# Sheet.net
KiCad netlist of a schematic drawn in Altium Designer
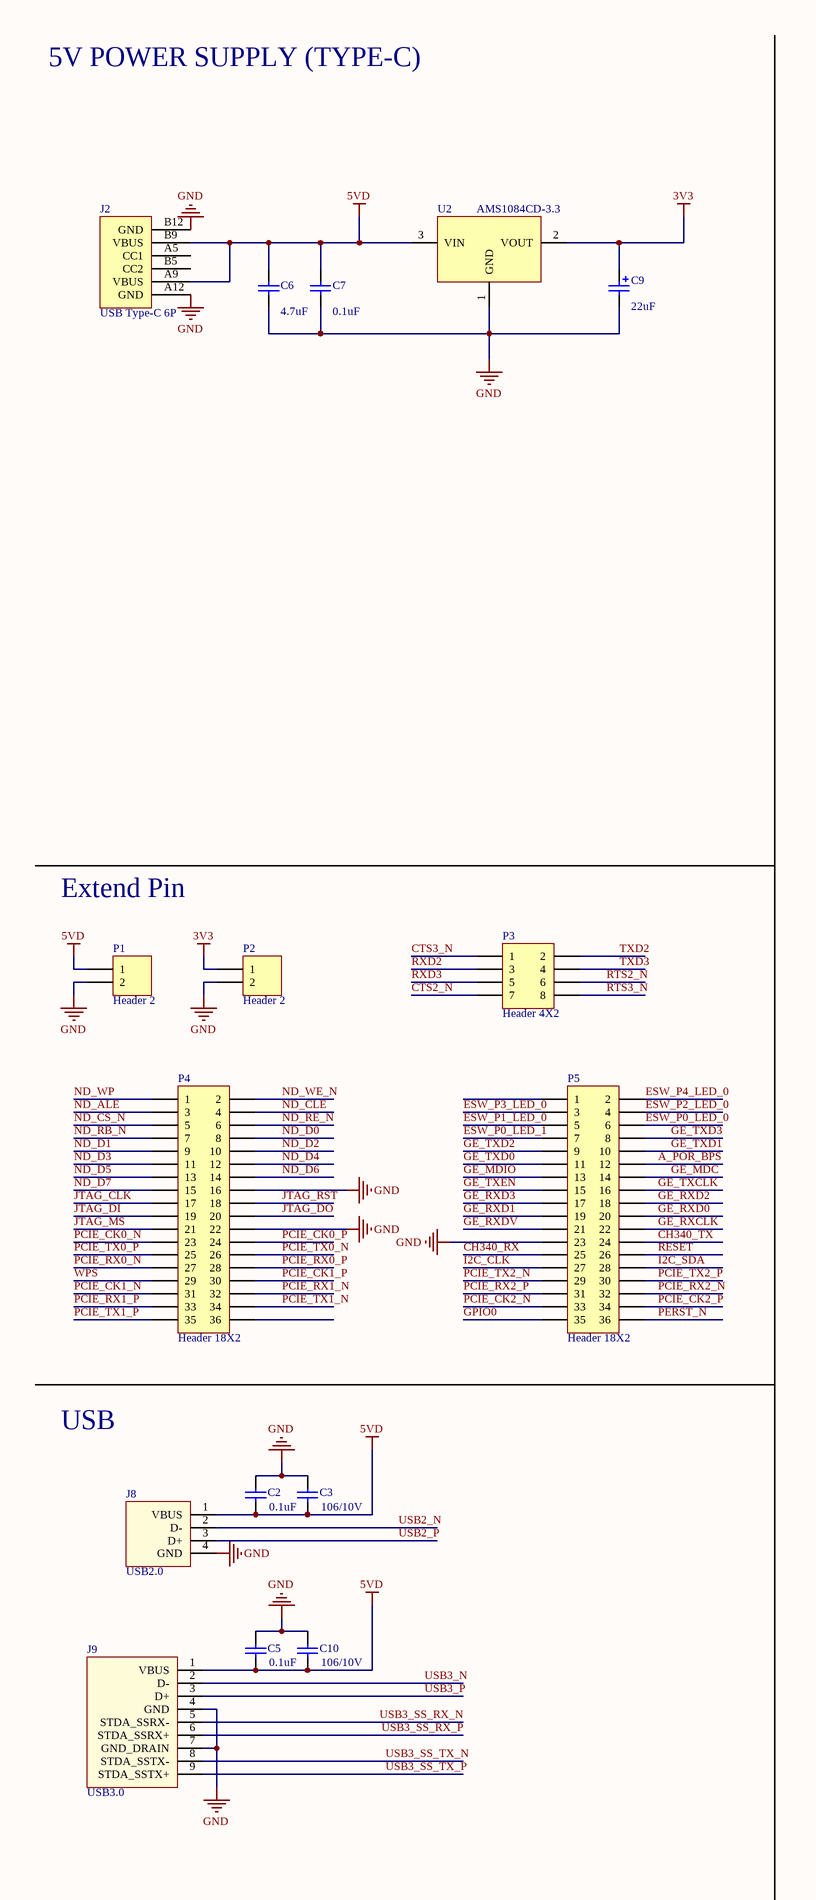
[diagram p0: Sheet.SchDoc, left]
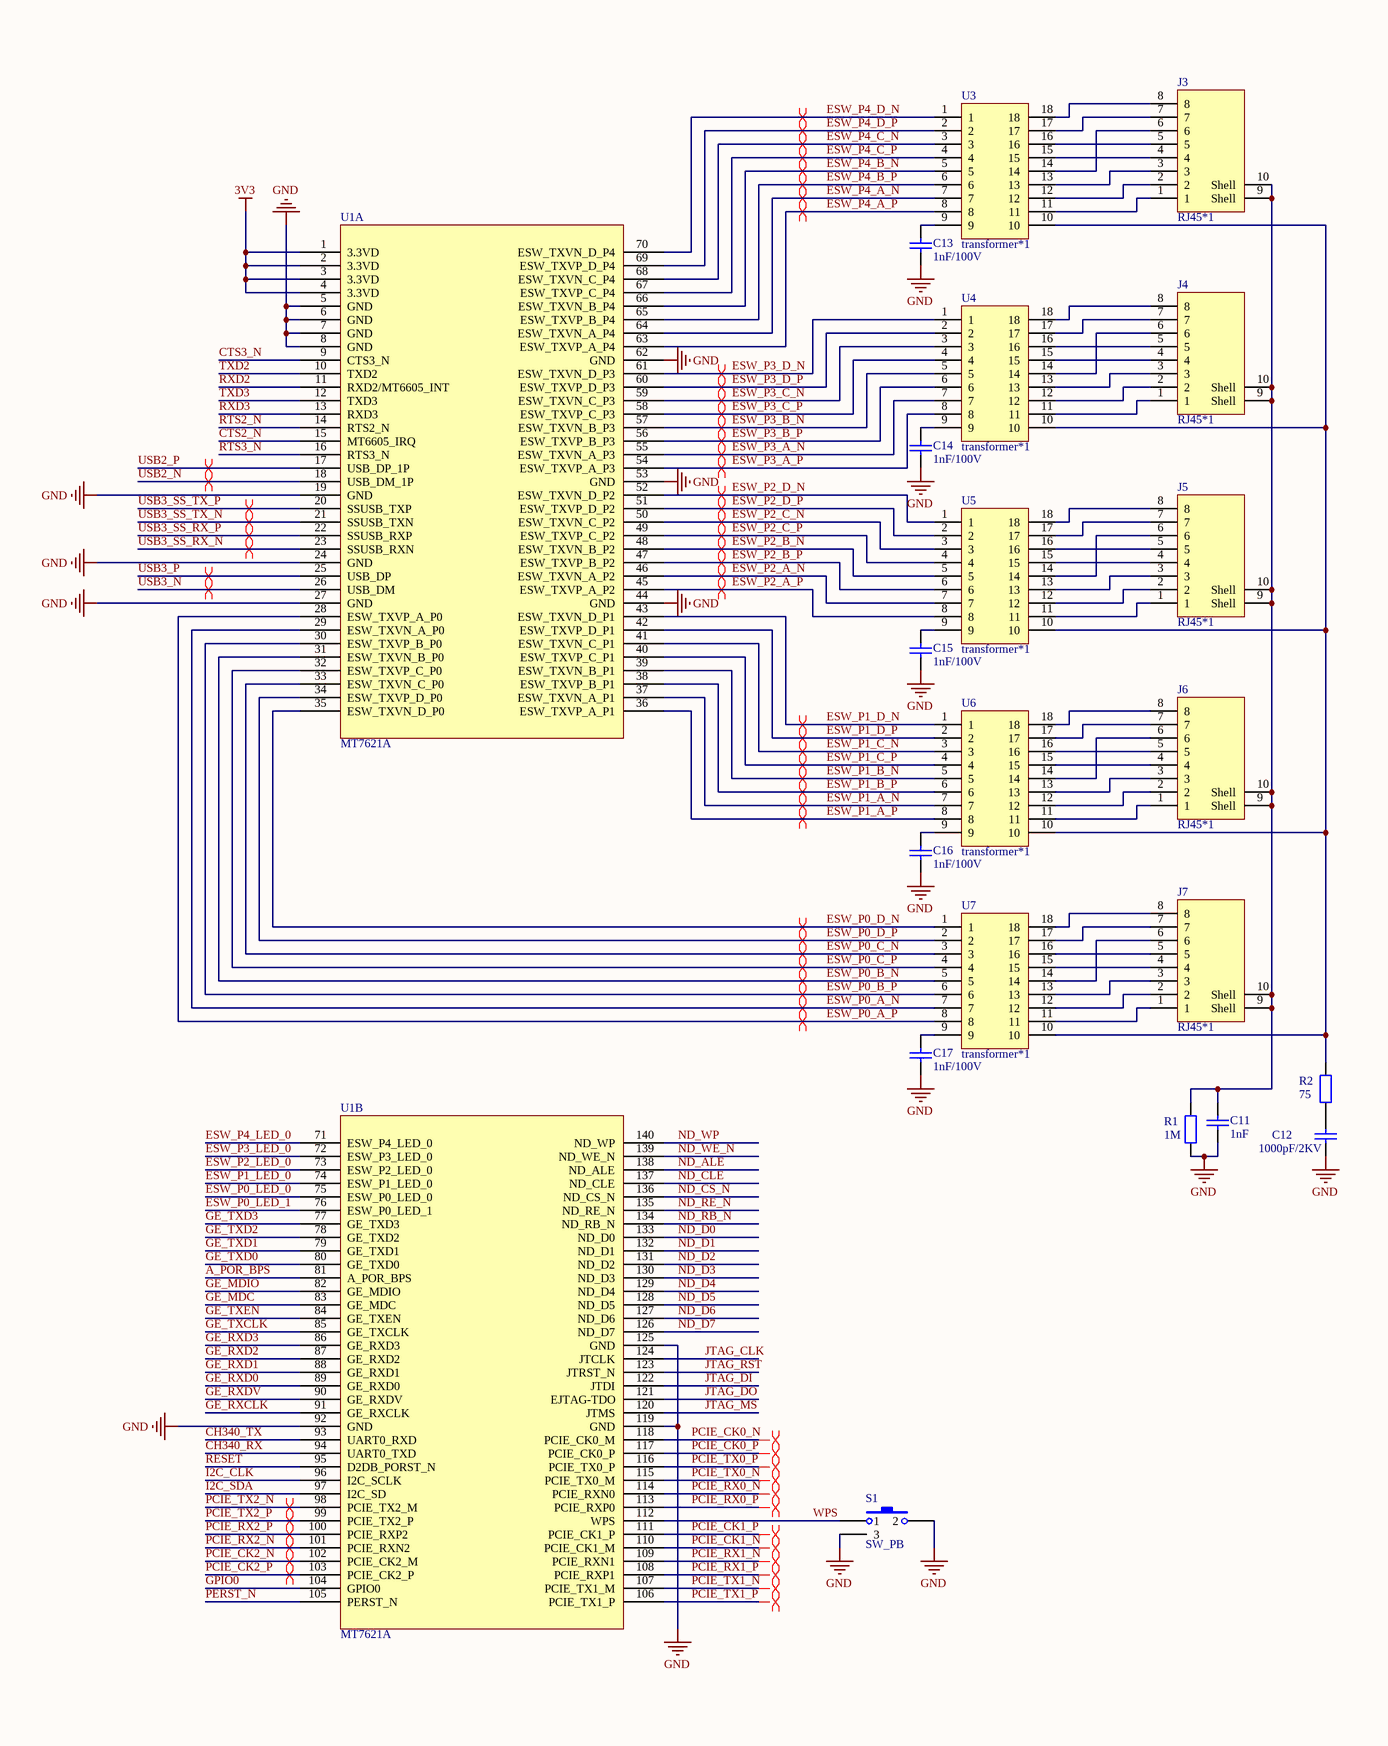
[diagram p1: Sheet.SchDoc, right]

(export (version "E")
  (design (tool "Eeschema 10.0.6"))
  (components
    (comp (ref "C2")
      (value "0.1uF")
      (footprint "6-0805")
      (description "Capacitor")
      (fields (field (name "Comment") "Cap") (field (name "PUBLISHER") "Altium Limited"))
      (libsource (lib "Miscellaneous Devices") (part "Cap"))
    )
    (comp (ref "C3")
      (value "106/10V")
      (footprint "6-0805")
      (description "Capacitor")
      (fields (field (name "Comment") "Cap") (field (name "PUBLISHER") "Altium Limited"))
      (libsource (lib "Miscellaneous Devices") (part "Cap"))
    )
    (comp (ref "C5")
      (value "0.1uF")
      (footprint "6-0805")
      (description "Capacitor")
      (fields (field (name "Comment") "Cap") (field (name "PUBLISHER") "Altium Limited"))
      (libsource (lib "Miscellaneous Devices") (part "Cap"))
    )
    (comp (ref "C6")
      (value "4.7uF")
      (footprint "6-0805")
      (description "Capacitor")
      (fields (field (name "Comment") "Cap") (field (name "PUBLISHER") "Altium Limited"))
      (libsource (lib "Miscellaneous Devices") (part "Cap"))
    )
    (comp (ref "C7")
      (value "0.1uF")
      (footprint "6-0805")
      (description "Capacitor")
      (fields (field (name "Comment") "Cap") (field (name "PUBLISHER") "Altium Limited"))
      (libsource (lib "Miscellaneous Devices") (part "Cap"))
    )
    (comp (ref "C9")
      (value "22uF")
      (footprint "3528B")
      (description "Polarized Capacitor (Axial)")
      (fields (field (name "Comment") "Cap Pol2") (field (name "PUBLISHER") "Altium Limited"))
      (libsource (lib "Miscellaneous Devices") (part "Cap Pol2"))
    )
    (comp (ref "C10")
      (value "106/10V")
      (footprint "6-0805")
      (description "Capacitor")
      (fields (field (name "Comment") "Cap") (field (name "PUBLISHER") "Altium Limited"))
      (libsource (lib "Miscellaneous Devices") (part "Cap"))
    )
    (comp (ref "C11")
      (value "1nF")
      (footprint "8-1206")
      (description "Capacitor")
      (fields (field (name "Comment") "Cap") (field (name "PUBLISHER") "Altium Limited"))
      (libsource (lib "Miscellaneous Devices") (part "Cap"))
    )
    (comp (ref "C12")
      (value "1000pF/2KV")
      (footprint "8-1206")
      (description "Capacitor")
      (fields (field (name "Comment") "Cap") (field (name "PUBLISHER") "Altium Limited"))
      (libsource (lib "Miscellaneous Devices") (part "Cap"))
    )
    (comp (ref "C13")
      (value "1nF/100V")
      (footprint "6-0805")
      (description "Capacitor")
      (fields (field (name "Comment") "Cap") (field (name "PUBLISHER") "Altium Limited"))
      (libsource (lib "Miscellaneous Devices") (part "Cap"))
    )
    (comp (ref "C14")
      (value "1nF/100V")
      (footprint "6-0805")
      (description "Capacitor")
      (fields (field (name "Comment") "Cap") (field (name "PUBLISHER") "Altium Limited"))
      (libsource (lib "Miscellaneous Devices") (part "Cap"))
    )
    (comp (ref "C15")
      (value "1nF/100V")
      (footprint "6-0805")
      (description "Capacitor")
      (fields (field (name "Comment") "Cap") (field (name "PUBLISHER") "Altium Limited"))
      (libsource (lib "Miscellaneous Devices") (part "Cap"))
    )
    (comp (ref "C16")
      (value "1nF/100V")
      (footprint "6-0805")
      (description "Capacitor")
      (fields (field (name "Comment") "Cap") (field (name "PUBLISHER") "Altium Limited"))
      (libsource (lib "Miscellaneous Devices") (part "Cap"))
    )
    (comp (ref "C17")
      (value "1nF/100V")
      (footprint "6-0805")
      (description "Capacitor")
      (fields (field (name "Comment") "Cap") (field (name "PUBLISHER") "Altium Limited"))
      (libsource (lib "Miscellaneous Devices") (part "Cap"))
    )
    (comp (ref "J2")
      (value "USB Type-C 6P")
      (footprint "USB Type-C 6P")
      (libsource (lib "7621_cmp") (part "USB Type-C 6P"))
    )
    (comp (ref "J3") (value "RJ45*1") (libsource (lib "7621_cmp") (part "RJ45*1")))
    (comp (ref "J4") (value "RJ45*1") (libsource (lib "7621_cmp") (part "RJ45*1")))
    (comp (ref "J5") (value "RJ45*1") (libsource (lib "7621_cmp") (part "RJ45*1")))
    (comp (ref "J6") (value "RJ45*1") (libsource (lib "7621_cmp") (part "RJ45*1")))
    (comp (ref "J7") (value "RJ45*1") (libsource (lib "7621_cmp") (part "RJ45*1")))
    (comp (ref "J8") (value "USB2.0") (footprint "USB2.0") (libsource (lib "7621_cmp") (part "USB2.0")))
    (comp (ref "J9") (value "USB3.0") (footprint "USB3.0_0") (libsource (lib "7621_cmp") (part "USB3.0")))
    (comp (ref "P1")
      (value "Header 2")
      (footprint "HDR1X2")
      (description "Header, 2-Pin")
      (fields (field (name "PUBLISHER") "Altium Limited"))
      (libsource (lib "Miscellaneous Connectors") (part "Header 2"))
    )
    (comp (ref "P2")
      (value "Header 2")
      (footprint "HDR1X2")
      (description "Header, 2-Pin")
      (fields (field (name "PUBLISHER") "Altium Limited"))
      (libsource (lib "Miscellaneous Connectors") (part "Header 2"))
    )
    (comp (ref "P3")
      (value "Header 4X2")
      (footprint "HDR2X4")
      (description "Header, 4-Pin, Dual row")
      (fields (field (name "PUBLISHER") "Altium Limited"))
      (libsource (lib "Miscellaneous Connectors") (part "Header 4X2"))
    )
    (comp (ref "P4")
      (value "Header 18X2")
      (footprint "HDR2X18")
      (description "Header, 18-Pin, Dual row")
      (fields (field (name "PUBLISHER") "Altium Limited"))
      (libsource (lib "Miscellaneous Connectors") (part "Header 18X2"))
    )
    (comp (ref "P5")
      (value "Header 18X2")
      (footprint "HDR2X18")
      (description "Header, 18-Pin, Dual row")
      (fields (field (name "PUBLISHER") "Altium Limited"))
      (libsource (lib "Miscellaneous Connectors") (part "Header 18X2"))
    )
    (comp (ref "R1")
      (value "1M")
      (footprint "8-1206")
      (description "Resistor")
      (fields (field (name "Comment") "Res2") (field (name "PUBLISHER") "Altium Limited"))
      (libsource (lib "Miscellaneous Devices") (part "Res2"))
    )
    (comp (ref "R2")
      (value "75")
      (footprint "8-1206")
      (description "Resistor")
      (fields (field (name "Comment") "Res2") (field (name "PUBLISHER") "Altium Limited"))
      (libsource (lib "Miscellaneous Devices") (part "Res2"))
    )
    (comp (ref "S1") (value "SW_PB") (footprint "SW_PB") (libsource (lib "7621_cmp") (part "SW_PB")))
    (comp (ref "U1") (value "MT7621A") (footprint "HLK-7621") (libsource (lib "7621_cmp") (part "MT7621A")))
    (comp (ref "U2")
      (value "AMS1084CD-3.3")
      (footprint "TO252")
      (libsource (lib "7621_cmp") (part "AMS1084CD-3.3"))
    )
    (comp (ref "U3")
      (value "transformer*1")
      (footprint "transformer_G1801D")
      (libsource (lib "7621_cmp") (part "transformer*1"))
    )
    (comp (ref "U4")
      (value "transformer*1")
      (footprint "transformer_G1801D")
      (libsource (lib "7621_cmp") (part "transformer*1"))
    )
    (comp (ref "U5")
      (value "transformer*1")
      (footprint "transformer_G1801D")
      (libsource (lib "7621_cmp") (part "transformer*1"))
    )
    (comp (ref "U6")
      (value "transformer*1")
      (footprint "transformer_G1801D")
      (libsource (lib "7621_cmp") (part "transformer*1"))
    )
    (comp (ref "U7")
      (value "transformer*1")
      (footprint "transformer_G1801D")
      (libsource (lib "7621_cmp") (part "transformer*1"))
    )
  )
  (nets
    (net (code "1") (name "/A_POR_BPS") (class "Default")
      (node (ref "P5") (pin "12") (pinfunction "12_12") (pintype "passive"))
      (node (ref "U1") (pin "81") (pinfunction "A_POR_BPS_81") (pintype "passive"))
    )
    (net (code "2") (name "/CH340_RX") (class "Default")
      (node (ref "P5") (pin "25") (pinfunction "25_25") (pintype "passive"))
      (node (ref "U1") (pin "94") (pinfunction "UART0_TXD_94") (pintype "passive"))
    )
    (net (code "3") (name "/CH340_TX") (class "Default")
      (node (ref "P5") (pin "24") (pinfunction "24_24") (pintype "passive"))
      (node (ref "U1") (pin "93") (pinfunction "UART0_RXD_93") (pintype "passive"))
    )
    (net (code "4") (name "/CTS2_N") (class "Default")
      (node (ref "P3") (pin "7") (pinfunction "7_7") (pintype "passive"))
      (node (ref "U1") (pin "15") (pinfunction "MT6605_IRQ_15") (pintype "passive"))
    )
    (net (code "5") (name "/CTS3_N") (class "Default")
      (node (ref "P3") (pin "1") (pinfunction "1_1") (pintype "passive"))
      (node (ref "U1") (pin "9") (pinfunction "CTS3_N_9") (pintype "passive"))
    )
    (net (code "6") (name "/ESW_P0_A_N") (class "Default")
      (node (ref "U1") (pin "29") (pinfunction "ESW_TXVN_A_P0_29") (pintype "passive"))
      (node (ref "U7") (pin "7") (pinfunction "7_7") (pintype "passive"))
    )
    (net (code "7") (name "/ESW_P0_A_P") (class "Default")
      (node (ref "U1") (pin "28") (pinfunction "ESW_TXVP_A_P0_28") (pintype "passive"))
      (node (ref "U7") (pin "8") (pinfunction "8_8") (pintype "passive"))
    )
    (net (code "8") (name "/ESW_P0_B_N") (class "Default")
      (node (ref "U1") (pin "31") (pinfunction "ESW_TXVN_B_P0_31") (pintype "passive"))
      (node (ref "U7") (pin "5") (pinfunction "5_5") (pintype "passive"))
    )
    (net (code "9") (name "/ESW_P0_B_P") (class "Default")
      (node (ref "U1") (pin "30") (pinfunction "ESW_TXVP_B_P0_30") (pintype "passive"))
      (node (ref "U7") (pin "6") (pinfunction "6_6") (pintype "passive"))
    )
    (net (code "10") (name "/ESW_P0_C_N") (class "Default")
      (node (ref "U1") (pin "33") (pinfunction "ESW_TXVN_C_P0_33") (pintype "passive"))
      (node (ref "U7") (pin "3") (pinfunction "3_3") (pintype "passive"))
    )
    (net (code "11") (name "/ESW_P0_C_P") (class "Default")
      (node (ref "U1") (pin "32") (pinfunction "ESW_TXVP_C_P0_32") (pintype "passive"))
      (node (ref "U7") (pin "4") (pinfunction "4_4") (pintype "passive"))
    )
    (net (code "12") (name "/ESW_P0_D_N") (class "Default")
      (node (ref "U1") (pin "35") (pinfunction "ESW_TXVN_D_P0_35") (pintype "passive"))
      (node (ref "U7") (pin "1") (pinfunction "1_1") (pintype "passive"))
    )
    (net (code "13") (name "/ESW_P0_D_P") (class "Default")
      (node (ref "U1") (pin "34") (pinfunction "ESW_TXVP_D_P0_34") (pintype "passive"))
      (node (ref "U7") (pin "2") (pinfunction "2_2") (pintype "passive"))
    )
    (net (code "14") (name "/ESW_P0_LED_0") (class "Default")
      (node (ref "P5") (pin "6") (pinfunction "6_6") (pintype "passive"))
      (node (ref "U1") (pin "75") (pinfunction "ESW_P0_LED_0_75") (pintype "passive"))
    )
    (net (code "15") (name "/ESW_P0_LED_1") (class "Default")
      (node (ref "P5") (pin "7") (pinfunction "7_7") (pintype "passive"))
      (node (ref "U1") (pin "76") (pinfunction "ESW_P0_LED_1_76") (pintype "passive"))
    )
    (net (code "16") (name "/ESW_P1_A_N") (class "Default")
      (node (ref "U1") (pin "37") (pinfunction "ESW_TXVN_A_P1_37") (pintype "passive"))
      (node (ref "U6") (pin "7") (pinfunction "7_7") (pintype "passive"))
    )
    (net (code "17") (name "/ESW_P1_A_P") (class "Default")
      (node (ref "U1") (pin "36") (pinfunction "ESW_TXVP_A_P1_36") (pintype "passive"))
      (node (ref "U6") (pin "8") (pinfunction "8_8") (pintype "passive"))
    )
    (net (code "18") (name "/ESW_P1_B_N") (class "Default")
      (node (ref "U1") (pin "39") (pinfunction "ESW_TXVN_B_P1_39") (pintype "passive"))
      (node (ref "U6") (pin "5") (pinfunction "5_5") (pintype "passive"))
    )
    (net (code "19") (name "/ESW_P1_B_P") (class "Default")
      (node (ref "U1") (pin "38") (pinfunction "ESW_TXVP_B_P1_38") (pintype "passive"))
      (node (ref "U6") (pin "6") (pinfunction "6_6") (pintype "passive"))
    )
    (net (code "20") (name "/ESW_P1_C_N") (class "Default")
      (node (ref "U1") (pin "41") (pinfunction "ESW_TXVN_C_P1_41") (pintype "passive"))
      (node (ref "U6") (pin "3") (pinfunction "3_3") (pintype "passive"))
    )
    (net (code "21") (name "/ESW_P1_C_P") (class "Default")
      (node (ref "U1") (pin "40") (pinfunction "ESW_TXVP_C_P1_40") (pintype "passive"))
      (node (ref "U6") (pin "4") (pinfunction "4_4") (pintype "passive"))
    )
    (net (code "22") (name "/ESW_P1_D_N") (class "Default")
      (node (ref "U1") (pin "43") (pinfunction "ESW_TXVN_D_P1_43") (pintype "passive"))
      (node (ref "U6") (pin "1") (pinfunction "1_1") (pintype "passive"))
    )
    (net (code "23") (name "/ESW_P1_D_P") (class "Default")
      (node (ref "U1") (pin "42") (pinfunction "ESW_TXVP_D_P1_42") (pintype "passive"))
      (node (ref "U6") (pin "2") (pinfunction "2_2") (pintype "passive"))
    )
    (net (code "24") (name "/ESW_P1_LED_0") (class "Default")
      (node (ref "P5") (pin "5") (pinfunction "5_5") (pintype "passive"))
      (node (ref "U1") (pin "74") (pinfunction "ESW_P1_LED_0_74") (pintype "passive"))
    )
    (net (code "25") (name "/ESW_P2_A_N") (class "Default")
      (node (ref "U1") (pin "46") (pinfunction "ESW_TXVN_A_P2_46") (pintype "passive"))
      (node (ref "U5") (pin "7") (pinfunction "7_7") (pintype "passive"))
    )
    (net (code "26") (name "/ESW_P2_A_P") (class "Default")
      (node (ref "U1") (pin "45") (pinfunction "ESW_TXVP_A_P2_45") (pintype "passive"))
      (node (ref "U5") (pin "8") (pinfunction "8_8") (pintype "passive"))
    )
    (net (code "27") (name "/ESW_P2_B_N") (class "Default")
      (node (ref "U1") (pin "48") (pinfunction "ESW_TXVN_B_P2_48") (pintype "passive"))
      (node (ref "U5") (pin "5") (pinfunction "5_5") (pintype "passive"))
    )
    (net (code "28") (name "/ESW_P2_B_P") (class "Default")
      (node (ref "U1") (pin "47") (pinfunction "ESW_TXVP_B_P2_47") (pintype "passive"))
      (node (ref "U5") (pin "6") (pinfunction "6_6") (pintype "passive"))
    )
    (net (code "29") (name "/ESW_P2_C_N") (class "Default")
      (node (ref "U1") (pin "50") (pinfunction "ESW_TXVN_C_P2_50") (pintype "passive"))
      (node (ref "U5") (pin "3") (pinfunction "3_3") (pintype "passive"))
    )
    (net (code "30") (name "/ESW_P2_C_P") (class "Default")
      (node (ref "U1") (pin "49") (pinfunction "ESW_TXVP_C_P2_49") (pintype "passive"))
      (node (ref "U5") (pin "4") (pinfunction "4_4") (pintype "passive"))
    )
    (net (code "31") (name "/ESW_P2_D_N") (class "Default")
      (node (ref "U1") (pin "52") (pinfunction "ESW_TXVN_D_P2_52") (pintype "passive"))
      (node (ref "U5") (pin "1") (pinfunction "1_1") (pintype "passive"))
    )
    (net (code "32") (name "/ESW_P2_D_P") (class "Default")
      (node (ref "U1") (pin "51") (pinfunction "ESW_TXVP_D_P2_51") (pintype "passive"))
      (node (ref "U5") (pin "2") (pinfunction "2_2") (pintype "passive"))
    )
    (net (code "33") (name "/ESW_P2_LED_0") (class "Default")
      (node (ref "P5") (pin "4") (pinfunction "4_4") (pintype "passive"))
      (node (ref "U1") (pin "73") (pinfunction "ESW_P2_LED_0_73") (pintype "passive"))
    )
    (net (code "34") (name "/ESW_P3_A_N") (class "Default")
      (node (ref "U1") (pin "55") (pinfunction "ESW_TXVN_A_P3_55") (pintype "passive"))
      (node (ref "U4") (pin "7") (pinfunction "7_7") (pintype "passive"))
    )
    (net (code "35") (name "/ESW_P3_A_P") (class "Default")
      (node (ref "U1") (pin "54") (pinfunction "ESW_TXVP_A_P3_54") (pintype "passive"))
      (node (ref "U4") (pin "8") (pinfunction "8_8") (pintype "passive"))
    )
    (net (code "36") (name "/ESW_P3_B_N") (class "Default")
      (node (ref "U1") (pin "57") (pinfunction "ESW_TXVN_B_P3_57") (pintype "passive"))
      (node (ref "U4") (pin "5") (pinfunction "5_5") (pintype "passive"))
    )
    (net (code "37") (name "/ESW_P3_B_P") (class "Default")
      (node (ref "U1") (pin "56") (pinfunction "ESW_TXVP_B_P3_56") (pintype "passive"))
      (node (ref "U4") (pin "6") (pinfunction "6_6") (pintype "passive"))
    )
    (net (code "38") (name "/ESW_P3_C_N") (class "Default")
      (node (ref "U1") (pin "59") (pinfunction "ESW_TXVN_C_P3_59") (pintype "passive"))
      (node (ref "U4") (pin "3") (pinfunction "3_3") (pintype "passive"))
    )
    (net (code "39") (name "/ESW_P3_C_P") (class "Default")
      (node (ref "U1") (pin "58") (pinfunction "ESW_TXVP_C_P3_58") (pintype "passive"))
      (node (ref "U4") (pin "4") (pinfunction "4_4") (pintype "passive"))
    )
    (net (code "40") (name "/ESW_P3_D_N") (class "Default")
      (node (ref "U1") (pin "61") (pinfunction "ESW_TXVN_D_P3_61") (pintype "passive"))
      (node (ref "U4") (pin "1") (pinfunction "1_1") (pintype "passive"))
    )
    (net (code "41") (name "/ESW_P3_D_P") (class "Default")
      (node (ref "U1") (pin "60") (pinfunction "ESW_TXVP_D_P3_60") (pintype "passive"))
      (node (ref "U4") (pin "2") (pinfunction "2_2") (pintype "passive"))
    )
    (net (code "42") (name "/ESW_P3_LED_0") (class "Default")
      (node (ref "P5") (pin "3") (pinfunction "3_3") (pintype "passive"))
      (node (ref "U1") (pin "72") (pinfunction "ESW_P3_LED_0_72") (pintype "passive"))
    )
    (net (code "43") (name "/ESW_P4_A_N") (class "Default")
      (node (ref "U1") (pin "64") (pinfunction "ESW_TXVN_A_P4_64") (pintype "passive"))
      (node (ref "U3") (pin "7") (pinfunction "7_7") (pintype "passive"))
    )
    (net (code "44") (name "/ESW_P4_A_P") (class "Default")
      (node (ref "U1") (pin "63") (pinfunction "ESW_TXVP_A_P4_63") (pintype "passive"))
      (node (ref "U3") (pin "8") (pinfunction "8_8") (pintype "passive"))
    )
    (net (code "45") (name "/ESW_P4_B_N") (class "Default")
      (node (ref "U1") (pin "66") (pinfunction "ESW_TXVN_B_P4_66") (pintype "passive"))
      (node (ref "U3") (pin "5") (pinfunction "5_5") (pintype "passive"))
    )
    (net (code "46") (name "/ESW_P4_B_P") (class "Default")
      (node (ref "U1") (pin "65") (pinfunction "ESW_TXVP_B_P4_65") (pintype "passive"))
      (node (ref "U3") (pin "6") (pinfunction "6_6") (pintype "passive"))
    )
    (net (code "47") (name "/ESW_P4_C_N") (class "Default")
      (node (ref "U1") (pin "68") (pinfunction "ESW_TXVN_C_P4_68") (pintype "passive"))
      (node (ref "U3") (pin "3") (pinfunction "3_3") (pintype "passive"))
    )
    (net (code "48") (name "/ESW_P4_C_P") (class "Default")
      (node (ref "U1") (pin "67") (pinfunction "ESW_TXVP_C_P4_67") (pintype "passive"))
      (node (ref "U3") (pin "4") (pinfunction "4_4") (pintype "passive"))
    )
    (net (code "49") (name "/ESW_P4_D_N") (class "Default")
      (node (ref "U1") (pin "70") (pinfunction "ESW_TXVN_D_P4_70") (pintype "passive"))
      (node (ref "U3") (pin "1") (pinfunction "1_1") (pintype "passive"))
    )
    (net (code "50") (name "/ESW_P4_D_P") (class "Default")
      (node (ref "U1") (pin "69") (pinfunction "ESW_TXVP_D_P4_69") (pintype "passive"))
      (node (ref "U3") (pin "2") (pinfunction "2_2") (pintype "passive"))
    )
    (net (code "51") (name "/ESW_P4_LED_0") (class "Default")
      (node (ref "P5") (pin "2") (pinfunction "2_2") (pintype "passive"))
      (node (ref "U1") (pin "71") (pinfunction "ESW_P4_LED_0_71") (pintype "passive"))
    )
    (net (code "52") (name "/GE_MDC") (class "Default")
      (node (ref "P5") (pin "14") (pinfunction "14_14") (pintype "passive"))
      (node (ref "U1") (pin "83") (pinfunction "GE_MDC_83") (pintype "passive"))
    )
    (net (code "53") (name "/GE_MDIO") (class "Default")
      (node (ref "P5") (pin "13") (pinfunction "13_13") (pintype "passive"))
      (node (ref "U1") (pin "82") (pinfunction "GE_MDIO_82") (pintype "passive"))
    )
    (net (code "54") (name "/GE_RXCLK") (class "Default")
      (node (ref "P5") (pin "22") (pinfunction "22_22") (pintype "passive"))
      (node (ref "U1") (pin "91") (pinfunction "GE_RXCLK_91") (pintype "passive"))
    )
    (net (code "55") (name "/GE_RXD0") (class "Default")
      (node (ref "P5") (pin "20") (pinfunction "20_20") (pintype "passive"))
      (node (ref "U1") (pin "89") (pinfunction "GE_RXD0_89") (pintype "passive"))
    )
    (net (code "56") (name "/GE_RXD1") (class "Default")
      (node (ref "P5") (pin "19") (pinfunction "19_19") (pintype "passive"))
      (node (ref "U1") (pin "88") (pinfunction "GE_RXD1_88") (pintype "passive"))
    )
    (net (code "57") (name "/GE_RXD2") (class "Default")
      (node (ref "P5") (pin "18") (pinfunction "18_18") (pintype "passive"))
      (node (ref "U1") (pin "87") (pinfunction "GE_RXD2_87") (pintype "passive"))
    )
    (net (code "58") (name "/GE_RXD3") (class "Default")
      (node (ref "P5") (pin "17") (pinfunction "17_17") (pintype "passive"))
      (node (ref "U1") (pin "86") (pinfunction "GE_RXD3_86") (pintype "passive"))
    )
    (net (code "59") (name "/GE_RXDV") (class "Default")
      (node (ref "P5") (pin "21") (pinfunction "21_21") (pintype "passive"))
      (node (ref "U1") (pin "90") (pinfunction "GE_RXDV_90") (pintype "passive"))
    )
    (net (code "60") (name "/GE_TXCLK") (class "Default")
      (node (ref "P5") (pin "16") (pinfunction "16_16") (pintype "passive"))
      (node (ref "U1") (pin "85") (pinfunction "GE_TXCLK_85") (pintype "passive"))
    )
    (net (code "61") (name "/GE_TXD0") (class "Default")
      (node (ref "P5") (pin "11") (pinfunction "11_11") (pintype "passive"))
      (node (ref "U1") (pin "80") (pinfunction "GE_TXD0_80") (pintype "passive"))
    )
    (net (code "62") (name "/GE_TXD1") (class "Default")
      (node (ref "P5") (pin "10") (pinfunction "10_10") (pintype "passive"))
      (node (ref "U1") (pin "79") (pinfunction "GE_TXD1_79") (pintype "passive"))
    )
    (net (code "63") (name "/GE_TXD2") (class "Default")
      (node (ref "P5") (pin "9") (pinfunction "9_9") (pintype "passive"))
      (node (ref "U1") (pin "78") (pinfunction "GE_TXD2_78") (pintype "passive"))
    )
    (net (code "64") (name "/GE_TXD3") (class "Default")
      (node (ref "P5") (pin "8") (pinfunction "8_8") (pintype "passive"))
      (node (ref "U1") (pin "77") (pinfunction "GE_TXD3_77") (pintype "passive"))
    )
    (net (code "65") (name "/GE_TXEN") (class "Default")
      (node (ref "P5") (pin "15") (pinfunction "15_15") (pintype "passive"))
      (node (ref "U1") (pin "84") (pinfunction "GE_TXEN_84") (pintype "passive"))
    )
    (net (code "66") (name "/GPIO0") (class "Default")
      (node (ref "P5") (pin "35") (pinfunction "35_35") (pintype "passive"))
      (node (ref "U1") (pin "104") (pinfunction "GPIO0_104") (pintype "passive"))
    )
    (net (code "67") (name "/I2C_CLK") (class "Default")
      (node (ref "P5") (pin "27") (pinfunction "27_27") (pintype "passive"))
      (node (ref "U1") (pin "96") (pinfunction "I2C_SCLK_96") (pintype "passive"))
    )
    (net (code "68") (name "/I2C_SDA") (class "Default")
      (node (ref "P5") (pin "28") (pinfunction "28_28") (pintype "passive"))
      (node (ref "U1") (pin "97") (pinfunction "I2C_SD_97") (pintype "passive"))
    )
    (net (code "69") (name "/JTAG_CLK") (class "Default")
      (node (ref "P4") (pin "17") (pinfunction "17_17") (pintype "passive"))
      (node (ref "U1") (pin "124") (pinfunction "JTCLK_124") (pintype "passive"))
    )
    (net (code "70") (name "/JTAG_DI") (class "Default")
      (node (ref "P4") (pin "19") (pinfunction "19_19") (pintype "passive"))
      (node (ref "U1") (pin "122") (pinfunction "JTDI_122") (pintype "passive"))
    )
    (net (code "71") (name "/JTAG_DO") (class "Default")
      (node (ref "P4") (pin "20") (pinfunction "20_20") (pintype "passive"))
      (node (ref "U1") (pin "121") (pinfunction "EJTAG-TDO_121") (pintype "passive"))
    )
    (net (code "72") (name "/JTAG_MS") (class "Default")
      (node (ref "P4") (pin "21") (pinfunction "21_21") (pintype "passive"))
      (node (ref "U1") (pin "120") (pinfunction "JTMS_120") (pintype "passive"))
    )
    (net (code "73") (name "/JTAG_RST") (class "Default")
      (node (ref "P4") (pin "18") (pinfunction "18_18") (pintype "passive"))
      (node (ref "U1") (pin "123") (pinfunction "JTRST_N_123") (pintype "passive"))
    )
    (net (code "74") (name "/ND_ALE") (class "Default")
      (node (ref "P4") (pin "3") (pinfunction "3_3") (pintype "passive"))
      (node (ref "U1") (pin "138") (pinfunction "ND_ALE_138") (pintype "passive"))
    )
    (net (code "75") (name "/ND_CLE") (class "Default")
      (node (ref "P4") (pin "4") (pinfunction "4_4") (pintype "passive"))
      (node (ref "U1") (pin "137") (pinfunction "ND_CLE_137") (pintype "passive"))
    )
    (net (code "76") (name "/ND_CS_N") (class "Default")
      (node (ref "P4") (pin "5") (pinfunction "5_5") (pintype "passive"))
      (node (ref "U1") (pin "136") (pinfunction "ND_CS_N_136") (pintype "passive"))
    )
    (net (code "77") (name "/ND_D0") (class "Default")
      (node (ref "P4") (pin "8") (pinfunction "8_8") (pintype "passive"))
      (node (ref "U1") (pin "133") (pinfunction "ND_D0_133") (pintype "passive"))
    )
    (net (code "78") (name "/ND_D1") (class "Default")
      (node (ref "P4") (pin "9") (pinfunction "9_9") (pintype "passive"))
      (node (ref "U1") (pin "132") (pinfunction "ND_D1_132") (pintype "passive"))
    )
    (net (code "79") (name "/ND_D2") (class "Default")
      (node (ref "P4") (pin "10") (pinfunction "10_10") (pintype "passive"))
      (node (ref "U1") (pin "131") (pinfunction "ND_D2_131") (pintype "passive"))
    )
    (net (code "80") (name "/ND_D3") (class "Default")
      (node (ref "P4") (pin "11") (pinfunction "11_11") (pintype "passive"))
      (node (ref "U1") (pin "130") (pinfunction "ND_D3_130") (pintype "passive"))
    )
    (net (code "81") (name "/ND_D4") (class "Default")
      (node (ref "P4") (pin "12") (pinfunction "12_12") (pintype "passive"))
      (node (ref "U1") (pin "129") (pinfunction "ND_D4_129") (pintype "passive"))
    )
    (net (code "82") (name "/ND_D5") (class "Default")
      (node (ref "P4") (pin "13") (pinfunction "13_13") (pintype "passive"))
      (node (ref "U1") (pin "128") (pinfunction "ND_D5_128") (pintype "passive"))
    )
    (net (code "83") (name "/ND_D6") (class "Default")
      (node (ref "P4") (pin "14") (pinfunction "14_14") (pintype "passive"))
      (node (ref "U1") (pin "127") (pinfunction "ND_D6_127") (pintype "passive"))
    )
    (net (code "84") (name "/ND_D7") (class "Default")
      (node (ref "P4") (pin "15") (pinfunction "15_15") (pintype "passive"))
      (node (ref "U1") (pin "126") (pinfunction "ND_D7_126") (pintype "passive"))
    )
    (net (code "85") (name "/ND_RB_N") (class "Default")
      (node (ref "P4") (pin "7") (pinfunction "7_7") (pintype "passive"))
      (node (ref "U1") (pin "134") (pinfunction "ND_RB_N_134") (pintype "passive"))
    )
    (net (code "86") (name "/ND_RE_N") (class "Default")
      (node (ref "P4") (pin "6") (pinfunction "6_6") (pintype "passive"))
      (node (ref "U1") (pin "135") (pinfunction "ND_RE_N_135") (pintype "passive"))
    )
    (net (code "87") (name "/ND_WE_N") (class "Default")
      (node (ref "P4") (pin "2") (pinfunction "2_2") (pintype "passive"))
      (node (ref "U1") (pin "139") (pinfunction "ND_WE_N_139") (pintype "passive"))
    )
    (net (code "88") (name "/ND_WP") (class "Default")
      (node (ref "P4") (pin "1") (pinfunction "1_1") (pintype "passive"))
      (node (ref "U1") (pin "140") (pinfunction "ND_WP_140") (pintype "passive"))
    )
    (net (code "89") (name "/PCIE_CK0_N") (class "Default")
      (node (ref "P4") (pin "23") (pinfunction "23_23") (pintype "passive"))
      (node (ref "U1") (pin "118") (pinfunction "PCIE_CK0_M_118") (pintype "passive"))
    )
    (net (code "90") (name "/PCIE_CK0_P") (class "Default")
      (node (ref "P4") (pin "24") (pinfunction "24_24") (pintype "passive"))
      (node (ref "U1") (pin "117") (pinfunction "PCIE_CK0_P_117") (pintype "passive"))
    )
    (net (code "91") (name "/PCIE_CK1_N") (class "Default")
      (node (ref "P4") (pin "31") (pinfunction "31_31") (pintype "passive"))
      (node (ref "U1") (pin "110") (pinfunction "PCIE_CK1_M_110") (pintype "passive"))
    )
    (net (code "92") (name "/PCIE_CK1_P") (class "Default")
      (node (ref "P4") (pin "30") (pinfunction "30_30") (pintype "passive"))
      (node (ref "U1") (pin "111") (pinfunction "PCIE_CK1_P_111") (pintype "passive"))
    )
    (net (code "93") (name "/PCIE_CK2_N") (class "Default")
      (node (ref "P5") (pin "33") (pinfunction "33_33") (pintype "passive"))
      (node (ref "U1") (pin "102") (pinfunction "PCIE_CK2_M_102") (pintype "passive"))
    )
    (net (code "94") (name "/PCIE_CK2_P") (class "Default")
      (node (ref "P5") (pin "34") (pinfunction "34_34") (pintype "passive"))
      (node (ref "U1") (pin "103") (pinfunction "PCIE_CK2_P_103") (pintype "passive"))
    )
    (net (code "95") (name "/PCIE_RX0_N") (class "Default")
      (node (ref "P4") (pin "27") (pinfunction "27_27") (pintype "passive"))
      (node (ref "U1") (pin "114") (pinfunction "PCIE_RXN0_114") (pintype "passive"))
    )
    (net (code "96") (name "/PCIE_RX0_P") (class "Default")
      (node (ref "P4") (pin "28") (pinfunction "28_28") (pintype "passive"))
      (node (ref "U1") (pin "113") (pinfunction "PCIE_RXP0_113") (pintype "passive"))
    )
    (net (code "97") (name "/PCIE_RX1_N") (class "Default")
      (node (ref "P4") (pin "32") (pinfunction "32_32") (pintype "passive"))
      (node (ref "U1") (pin "109") (pinfunction "PCIE_RXN1_109") (pintype "passive"))
    )
    (net (code "98") (name "/PCIE_RX1_P") (class "Default")
      (node (ref "P4") (pin "33") (pinfunction "33_33") (pintype "passive"))
      (node (ref "U1") (pin "108") (pinfunction "PCIE_RXP1_108") (pintype "passive"))
    )
    (net (code "99") (name "/PCIE_RX2_N") (class "Default")
      (node (ref "P5") (pin "32") (pinfunction "32_32") (pintype "passive"))
      (node (ref "U1") (pin "101") (pinfunction "PCIE_RXN2_101") (pintype "passive"))
    )
    (net (code "100") (name "/PCIE_RX2_P") (class "Default")
      (node (ref "P5") (pin "31") (pinfunction "31_31") (pintype "passive"))
      (node (ref "U1") (pin "100") (pinfunction "PCIE_RXP2_100") (pintype "passive"))
    )
    (net (code "101") (name "/PCIE_TX0_N") (class "Default")
      (node (ref "P4") (pin "26") (pinfunction "26_26") (pintype "passive"))
      (node (ref "U1") (pin "115") (pinfunction "PCIE_TX0_M_115") (pintype "passive"))
    )
    (net (code "102") (name "/PCIE_TX0_P") (class "Default")
      (node (ref "P4") (pin "25") (pinfunction "25_25") (pintype "passive"))
      (node (ref "U1") (pin "116") (pinfunction "PCIE_TX0_P_116") (pintype "passive"))
    )
    (net (code "103") (name "/PCIE_TX1_N") (class "Default")
      (node (ref "P4") (pin "34") (pinfunction "34_34") (pintype "passive"))
      (node (ref "U1") (pin "107") (pinfunction "PCIE_TX1_M_107") (pintype "passive"))
    )
    (net (code "104") (name "/PCIE_TX1_P") (class "Default")
      (node (ref "P4") (pin "35") (pinfunction "35_35") (pintype "passive"))
      (node (ref "U1") (pin "106") (pinfunction "PCIE_TX1_P_106") (pintype "passive"))
    )
    (net (code "105") (name "/PCIE_TX2_N") (class "Default")
      (node (ref "P5") (pin "29") (pinfunction "29_29") (pintype "passive"))
      (node (ref "U1") (pin "98") (pinfunction "PCIE_TX2_M_98") (pintype "passive"))
    )
    (net (code "106") (name "/PCIE_TX2_P") (class "Default")
      (node (ref "P5") (pin "30") (pinfunction "30_30") (pintype "passive"))
      (node (ref "U1") (pin "99") (pinfunction "PCIE_TX2_P_99") (pintype "passive"))
    )
    (net (code "107") (name "/PERST_N") (class "Default")
      (node (ref "P5") (pin "36") (pinfunction "36_36") (pintype "passive"))
      (node (ref "U1") (pin "105") (pinfunction "PERST_N_105") (pintype "passive"))
    )
    (net (code "108") (name "/RESET") (class "Default")
      (node (ref "P5") (pin "26") (pinfunction "26_26") (pintype "passive"))
      (node (ref "U1") (pin "95") (pinfunction "D2DB_PORST_N_95") (pintype "passive"))
    )
    (net (code "109") (name "/RTS2_N") (class "Default")
      (node (ref "P3") (pin "6") (pinfunction "6_6") (pintype "passive"))
      (node (ref "U1") (pin "14") (pinfunction "RTS2_N_14") (pintype "passive"))
    )
    (net (code "110") (name "/RTS3_N") (class "Default")
      (node (ref "P3") (pin "8") (pinfunction "8_8") (pintype "passive"))
      (node (ref "U1") (pin "16") (pinfunction "RTS3_N_16") (pintype "passive"))
    )
    (net (code "111") (name "/RXD2") (class "Default")
      (node (ref "P3") (pin "3") (pinfunction "3_3") (pintype "passive"))
      (node (ref "U1") (pin "11") (pinfunction "RXD2/MT6605_INT_11") (pintype "passive"))
    )
    (net (code "112") (name "/RXD3") (class "Default")
      (node (ref "P3") (pin "5") (pinfunction "5_5") (pintype "passive"))
      (node (ref "U1") (pin "13") (pinfunction "RXD3_13") (pintype "passive"))
    )
    (net (code "113") (name "/TXD2") (class "Default")
      (node (ref "P3") (pin "2") (pinfunction "2_2") (pintype "passive"))
      (node (ref "U1") (pin "10") (pinfunction "TXD2_10") (pintype "passive"))
    )
    (net (code "114") (name "/TXD3") (class "Default")
      (node (ref "P3") (pin "4") (pinfunction "4_4") (pintype "passive"))
      (node (ref "U1") (pin "12") (pinfunction "TXD3_12") (pintype "passive"))
    )
    (net (code "115") (name "/USB2_N") (class "Default")
      (node (ref "J8") (pin "2") (pinfunction "D-_2") (pintype "passive"))
      (node (ref "U1") (pin "18") (pinfunction "USB_DM_1P_18") (pintype "passive"))
    )
    (net (code "116") (name "/USB2_P") (class "Default")
      (node (ref "J8") (pin "3") (pinfunction "D+_3") (pintype "passive"))
      (node (ref "U1") (pin "17") (pinfunction "USB_DP_1P_17") (pintype "passive"))
    )
    (net (code "117") (name "/USB3_N") (class "Default")
      (node (ref "J9") (pin "2") (pinfunction "D-_2") (pintype "passive"))
      (node (ref "U1") (pin "26") (pinfunction "USB_DM_26") (pintype "passive"))
    )
    (net (code "118") (name "/USB3_P") (class "Default")
      (node (ref "J9") (pin "3") (pinfunction "D+_3") (pintype "passive"))
      (node (ref "U1") (pin "25") (pinfunction "USB_DP_25") (pintype "passive"))
    )
    (net (code "119") (name "/USB3_SS_RX_N") (class "Default")
      (node (ref "J9") (pin "5") (pinfunction "STDA_SSRX-_5") (pintype "passive"))
      (node (ref "U1") (pin "23") (pinfunction "SSUSB_RXN_23") (pintype "passive"))
    )
    (net (code "120") (name "/USB3_SS_RX_P") (class "Default")
      (node (ref "J9") (pin "6") (pinfunction "STDA_SSRX+_6") (pintype "passive"))
      (node (ref "U1") (pin "22") (pinfunction "SSUSB_RXP_22") (pintype "passive"))
    )
    (net (code "121") (name "/USB3_SS_TX_N") (class "Default")
      (node (ref "J9") (pin "8") (pinfunction "STDA_SSTX-_8") (pintype "passive"))
      (node (ref "U1") (pin "21") (pinfunction "SSUSB_TXN_21") (pintype "passive"))
    )
    (net (code "122") (name "/USB3_SS_TX_P") (class "Default")
      (node (ref "J9") (pin "9") (pinfunction "STDA_SSTX+_9") (pintype "passive"))
      (node (ref "U1") (pin "20") (pinfunction "SSUSB_TXP_20") (pintype "passive"))
    )
    (net (code "123") (name "/WPS") (class "Default")
      (node (ref "P4") (pin "29") (pinfunction "29_29") (pintype "passive"))
      (node (ref "S1") (pin "1") (pinfunction "1_1") (pintype "passive"))
      (node (ref "U1") (pin "112") (pinfunction "WPS_112") (pintype "passive"))
    )
    (net (code "124") (name "3V3") (class "Default")
      (node (ref "C9") (pin "1") (pinfunction "1_1") (pintype "passive"))
      (node (ref "P2") (pin "1") (pinfunction "1_1") (pintype "passive"))
      (node (ref "U1") (pin "1") (pinfunction "3.3VD_1") (pintype "passive"))
      (node (ref "U1") (pin "2") (pinfunction "3.3VD_2") (pintype "passive"))
      (node (ref "U1") (pin "3") (pinfunction "3.3VD_3") (pintype "passive"))
      (node (ref "U1") (pin "4") (pinfunction "3.3VD_4") (pintype "passive"))
      (node (ref "U2") (pin "2") (pinfunction "VOUT_2") (pintype "passive"))
    )
    (net (code "125") (name "5VD") (class "Default")
      (node (ref "C10") (pin "1") (pinfunction "1_1") (pintype "passive"))
      (node (ref "C2") (pin "1") (pinfunction "1_1") (pintype "passive"))
      (node (ref "C3") (pin "1") (pinfunction "1_1") (pintype "passive"))
      (node (ref "C5") (pin "1") (pinfunction "1_1") (pintype "passive"))
      (node (ref "C6") (pin "2") (pinfunction "2_2") (pintype "passive"))
      (node (ref "C7") (pin "2") (pinfunction "2_2") (pintype "passive"))
      (node (ref "J2") (pin "A9") (pinfunction "VBUS_A9") (pintype "passive"))
      (node (ref "J2") (pin "B9") (pinfunction "VBUS_B9") (pintype "passive"))
      (node (ref "J8") (pin "1") (pinfunction "VBUS_1") (pintype "passive"))
      (node (ref "J9") (pin "1") (pinfunction "VBUS_1") (pintype "passive"))
      (node (ref "P1") (pin "1") (pinfunction "1_1") (pintype "passive"))
      (node (ref "U2") (pin "3") (pinfunction "VIN_3") (pintype "passive"))
    )
    (net (code "126") (name "GND") (class "Default")
      (node (ref "C10") (pin "2") (pinfunction "2_2") (pintype "passive"))
      (node (ref "C11") (pin "1") (pinfunction "1_1") (pintype "passive"))
      (node (ref "C12") (pin "2") (pinfunction "2_2") (pintype "passive"))
      (node (ref "C13") (pin "2") (pinfunction "2_2") (pintype "passive"))
      (node (ref "C14") (pin "2") (pinfunction "2_2") (pintype "passive"))
      (node (ref "C15") (pin "2") (pinfunction "2_2") (pintype "passive"))
      (node (ref "C16") (pin "2") (pinfunction "2_2") (pintype "passive"))
      (node (ref "C17") (pin "2") (pinfunction "2_2") (pintype "passive"))
      (node (ref "C2") (pin "2") (pinfunction "2_2") (pintype "passive"))
      (node (ref "C3") (pin "2") (pinfunction "2_2") (pintype "passive"))
      (node (ref "C5") (pin "2") (pinfunction "2_2") (pintype "passive"))
      (node (ref "C6") (pin "1") (pinfunction "1_1") (pintype "passive"))
      (node (ref "C7") (pin "1") (pinfunction "1_1") (pintype "passive"))
      (node (ref "C9") (pin "2") (pinfunction "2_2") (pintype "passive"))
      (node (ref "J2") (pin "A12") (pinfunction "GND_A12") (pintype "passive"))
      (node (ref "J2") (pin "B12") (pinfunction "GND_B12") (pintype "passive"))
      (node (ref "J8") (pin "4") (pinfunction "GND_4") (pintype "passive"))
      (node (ref "J9") (pin "4") (pinfunction "GND_4") (pintype "passive"))
      (node (ref "J9") (pin "7") (pinfunction "GND_DRAIN_7") (pintype "passive"))
      (node (ref "P1") (pin "2") (pinfunction "2_2") (pintype "passive"))
      (node (ref "P2") (pin "2") (pinfunction "2_2") (pintype "passive"))
      (node (ref "P4") (pin "16") (pinfunction "16_16") (pintype "passive"))
      (node (ref "P4") (pin "22") (pinfunction "22_22") (pintype "passive"))
      (node (ref "P5") (pin "23") (pinfunction "23_23") (pintype "passive"))
      (node (ref "R1") (pin "1") (pinfunction "1_1") (pintype "passive"))
      (node (ref "S1") (pin "2") (pinfunction "2_2") (pintype "passive"))
      (node (ref "S1") (pin "3") (pinfunction "3_3") (pintype "passive"))
      (node (ref "U1") (pin "119") (pinfunction "GND_119") (pintype "passive"))
      (node (ref "U1") (pin "125") (pinfunction "GND_125") (pintype "passive"))
      (node (ref "U1") (pin "19") (pinfunction "GND_19") (pintype "passive"))
      (node (ref "U1") (pin "24") (pinfunction "GND_24") (pintype "passive"))
      (node (ref "U1") (pin "27") (pinfunction "GND_27") (pintype "passive"))
      (node (ref "U1") (pin "44") (pinfunction "GND_44") (pintype "passive"))
      (node (ref "U1") (pin "5") (pinfunction "GND_5") (pintype "passive"))
      (node (ref "U1") (pin "53") (pinfunction "GND_53") (pintype "passive"))
      (node (ref "U1") (pin "6") (pinfunction "GND_6") (pintype "passive"))
      (node (ref "U1") (pin "62") (pinfunction "GND_62") (pintype "passive"))
      (node (ref "U1") (pin "7") (pinfunction "GND_7") (pintype "passive"))
      (node (ref "U1") (pin "8") (pinfunction "GND_8") (pintype "passive"))
      (node (ref "U1") (pin "92") (pinfunction "GND_92") (pintype "passive"))
      (node (ref "U2") (pin "1") (pinfunction "GND_1") (pintype "passive"))
    )
    (net (code "127") (name "Net-(C11-Pad2)") (class "Default")
      (node (ref "C11") (pin "2") (pinfunction "2_2") (pintype "passive"))
      (node (ref "J3") (pin "10") (pinfunction "Shell_10") (pintype "passive"))
      (node (ref "J3") (pin "9") (pinfunction "Shell_9") (pintype "passive"))
      (node (ref "J4") (pin "10") (pinfunction "Shell_10") (pintype "passive"))
      (node (ref "J4") (pin "9") (pinfunction "Shell_9") (pintype "passive"))
      (node (ref "J5") (pin "10") (pinfunction "Shell_10") (pintype "passive"))
      (node (ref "J5") (pin "9") (pinfunction "Shell_9") (pintype "passive"))
      (node (ref "J6") (pin "10") (pinfunction "Shell_10") (pintype "passive"))
      (node (ref "J6") (pin "9") (pinfunction "Shell_9") (pintype "passive"))
      (node (ref "J7") (pin "10") (pinfunction "Shell_10") (pintype "passive"))
      (node (ref "J7") (pin "9") (pinfunction "Shell_9") (pintype "passive"))
      (node (ref "R1") (pin "2") (pinfunction "2_2") (pintype "passive"))
    )
    (net (code "128") (name "Net-(C12-Pad1)") (class "Default")
      (node (ref "C12") (pin "1") (pinfunction "1_1") (pintype "passive"))
      (node (ref "R2") (pin "1") (pinfunction "1_1") (pintype "passive"))
    )
    (net (code "129") (name "Net-(C13-Pad1)") (class "Default")
      (node (ref "C13") (pin "1") (pinfunction "1_1") (pintype "passive"))
      (node (ref "U3") (pin "9") (pinfunction "9_9") (pintype "passive"))
    )
    (net (code "130") (name "Net-(C14-Pad1)") (class "Default")
      (node (ref "C14") (pin "1") (pinfunction "1_1") (pintype "passive"))
      (node (ref "U4") (pin "9") (pinfunction "9_9") (pintype "passive"))
    )
    (net (code "131") (name "Net-(C15-Pad1)") (class "Default")
      (node (ref "C15") (pin "1") (pinfunction "1_1") (pintype "passive"))
      (node (ref "U5") (pin "9") (pinfunction "9_9") (pintype "passive"))
    )
    (net (code "132") (name "Net-(C16-Pad1)") (class "Default")
      (node (ref "C16") (pin "1") (pinfunction "1_1") (pintype "passive"))
      (node (ref "U6") (pin "9") (pinfunction "9_9") (pintype "passive"))
    )
    (net (code "133") (name "Net-(C17-Pad1)") (class "Default")
      (node (ref "C17") (pin "1") (pinfunction "1_1") (pintype "passive"))
      (node (ref "U7") (pin "9") (pinfunction "9_9") (pintype "passive"))
    )
    (net (code "134") (name "Net-(J3-Pad1)") (class "Default")
      (node (ref "J3") (pin "1") (pinfunction "1_1") (pintype "passive"))
      (node (ref "U3") (pin "11") (pinfunction "11_11") (pintype "passive"))
    )
    (net (code "135") (name "Net-(J3-Pad2)") (class "Default")
      (node (ref "J3") (pin "2") (pinfunction "2_2") (pintype "passive"))
      (node (ref "U3") (pin "12") (pinfunction "12_12") (pintype "passive"))
    )
    (net (code "136") (name "Net-(J3-Pad3)") (class "Default")
      (node (ref "J3") (pin "3") (pinfunction "3_3") (pintype "passive"))
      (node (ref "U3") (pin "13") (pinfunction "13_13") (pintype "passive"))
    )
    (net (code "137") (name "Net-(J3-Pad4)") (class "Default")
      (node (ref "J3") (pin "4") (pinfunction "4_4") (pintype "passive"))
      (node (ref "U3") (pin "15") (pinfunction "15_15") (pintype "passive"))
    )
    (net (code "138") (name "Net-(J3-Pad5)") (class "Default")
      (node (ref "J3") (pin "5") (pinfunction "5_5") (pintype "passive"))
      (node (ref "U3") (pin "16") (pinfunction "16_16") (pintype "passive"))
    )
    (net (code "139") (name "Net-(J3-Pad6)") (class "Default")
      (node (ref "J3") (pin "6") (pinfunction "6_6") (pintype "passive"))
      (node (ref "U3") (pin "14") (pinfunction "14_14") (pintype "passive"))
    )
    (net (code "140") (name "Net-(J3-Pad7)") (class "Default")
      (node (ref "J3") (pin "7") (pinfunction "7_7") (pintype "passive"))
      (node (ref "U3") (pin "17") (pinfunction "17_17") (pintype "passive"))
    )
    (net (code "141") (name "Net-(J3-Pad8)") (class "Default")
      (node (ref "J3") (pin "8") (pinfunction "8_8") (pintype "passive"))
      (node (ref "U3") (pin "18") (pinfunction "18_18") (pintype "passive"))
    )
    (net (code "142") (name "Net-(J4-Pad1)") (class "Default")
      (node (ref "J4") (pin "1") (pinfunction "1_1") (pintype "passive"))
      (node (ref "U4") (pin "11") (pinfunction "11_11") (pintype "passive"))
    )
    (net (code "143") (name "Net-(J4-Pad2)") (class "Default")
      (node (ref "J4") (pin "2") (pinfunction "2_2") (pintype "passive"))
      (node (ref "U4") (pin "12") (pinfunction "12_12") (pintype "passive"))
    )
    (net (code "144") (name "Net-(J4-Pad3)") (class "Default")
      (node (ref "J4") (pin "3") (pinfunction "3_3") (pintype "passive"))
      (node (ref "U4") (pin "13") (pinfunction "13_13") (pintype "passive"))
    )
    (net (code "145") (name "Net-(J4-Pad4)") (class "Default")
      (node (ref "J4") (pin "4") (pinfunction "4_4") (pintype "passive"))
      (node (ref "U4") (pin "15") (pinfunction "15_15") (pintype "passive"))
    )
    (net (code "146") (name "Net-(J4-Pad5)") (class "Default")
      (node (ref "J4") (pin "5") (pinfunction "5_5") (pintype "passive"))
      (node (ref "U4") (pin "16") (pinfunction "16_16") (pintype "passive"))
    )
    (net (code "147") (name "Net-(J4-Pad6)") (class "Default")
      (node (ref "J4") (pin "6") (pinfunction "6_6") (pintype "passive"))
      (node (ref "U4") (pin "14") (pinfunction "14_14") (pintype "passive"))
    )
    (net (code "148") (name "Net-(J4-Pad7)") (class "Default")
      (node (ref "J4") (pin "7") (pinfunction "7_7") (pintype "passive"))
      (node (ref "U4") (pin "17") (pinfunction "17_17") (pintype "passive"))
    )
    (net (code "149") (name "Net-(J4-Pad8)") (class "Default")
      (node (ref "J4") (pin "8") (pinfunction "8_8") (pintype "passive"))
      (node (ref "U4") (pin "18") (pinfunction "18_18") (pintype "passive"))
    )
    (net (code "150") (name "Net-(J5-Pad1)") (class "Default")
      (node (ref "J5") (pin "1") (pinfunction "1_1") (pintype "passive"))
      (node (ref "U5") (pin "11") (pinfunction "11_11") (pintype "passive"))
    )
    (net (code "151") (name "Net-(J5-Pad2)") (class "Default")
      (node (ref "J5") (pin "2") (pinfunction "2_2") (pintype "passive"))
      (node (ref "U5") (pin "12") (pinfunction "12_12") (pintype "passive"))
    )
    (net (code "152") (name "Net-(J5-Pad3)") (class "Default")
      (node (ref "J5") (pin "3") (pinfunction "3_3") (pintype "passive"))
      (node (ref "U5") (pin "13") (pinfunction "13_13") (pintype "passive"))
    )
    (net (code "153") (name "Net-(J5-Pad4)") (class "Default")
      (node (ref "J5") (pin "4") (pinfunction "4_4") (pintype "passive"))
      (node (ref "U5") (pin "15") (pinfunction "15_15") (pintype "passive"))
    )
    (net (code "154") (name "Net-(J5-Pad5)") (class "Default")
      (node (ref "J5") (pin "5") (pinfunction "5_5") (pintype "passive"))
      (node (ref "U5") (pin "16") (pinfunction "16_16") (pintype "passive"))
    )
    (net (code "155") (name "Net-(J5-Pad6)") (class "Default")
      (node (ref "J5") (pin "6") (pinfunction "6_6") (pintype "passive"))
      (node (ref "U5") (pin "14") (pinfunction "14_14") (pintype "passive"))
    )
    (net (code "156") (name "Net-(J5-Pad7)") (class "Default")
      (node (ref "J5") (pin "7") (pinfunction "7_7") (pintype "passive"))
      (node (ref "U5") (pin "17") (pinfunction "17_17") (pintype "passive"))
    )
    (net (code "157") (name "Net-(J5-Pad8)") (class "Default")
      (node (ref "J5") (pin "8") (pinfunction "8_8") (pintype "passive"))
      (node (ref "U5") (pin "18") (pinfunction "18_18") (pintype "passive"))
    )
    (net (code "158") (name "Net-(J6-Pad1)") (class "Default")
      (node (ref "J6") (pin "1") (pinfunction "1_1") (pintype "passive"))
      (node (ref "U6") (pin "11") (pinfunction "11_11") (pintype "passive"))
    )
    (net (code "159") (name "Net-(J6-Pad2)") (class "Default")
      (node (ref "J6") (pin "2") (pinfunction "2_2") (pintype "passive"))
      (node (ref "U6") (pin "12") (pinfunction "12_12") (pintype "passive"))
    )
    (net (code "160") (name "Net-(J6-Pad3)") (class "Default")
      (node (ref "J6") (pin "3") (pinfunction "3_3") (pintype "passive"))
      (node (ref "U6") (pin "13") (pinfunction "13_13") (pintype "passive"))
    )
    (net (code "161") (name "Net-(J6-Pad4)") (class "Default")
      (node (ref "J6") (pin "4") (pinfunction "4_4") (pintype "passive"))
      (node (ref "U6") (pin "15") (pinfunction "15_15") (pintype "passive"))
    )
    (net (code "162") (name "Net-(J6-Pad5)") (class "Default")
      (node (ref "J6") (pin "5") (pinfunction "5_5") (pintype "passive"))
      (node (ref "U6") (pin "16") (pinfunction "16_16") (pintype "passive"))
    )
    (net (code "163") (name "Net-(J6-Pad6)") (class "Default")
      (node (ref "J6") (pin "6") (pinfunction "6_6") (pintype "passive"))
      (node (ref "U6") (pin "14") (pinfunction "14_14") (pintype "passive"))
    )
    (net (code "164") (name "Net-(J6-Pad7)") (class "Default")
      (node (ref "J6") (pin "7") (pinfunction "7_7") (pintype "passive"))
      (node (ref "U6") (pin "17") (pinfunction "17_17") (pintype "passive"))
    )
    (net (code "165") (name "Net-(J6-Pad8)") (class "Default")
      (node (ref "J6") (pin "8") (pinfunction "8_8") (pintype "passive"))
      (node (ref "U6") (pin "18") (pinfunction "18_18") (pintype "passive"))
    )
    (net (code "166") (name "Net-(J7-Pad1)") (class "Default")
      (node (ref "J7") (pin "1") (pinfunction "1_1") (pintype "passive"))
      (node (ref "U7") (pin "11") (pinfunction "11_11") (pintype "passive"))
    )
    (net (code "167") (name "Net-(J7-Pad2)") (class "Default")
      (node (ref "J7") (pin "2") (pinfunction "2_2") (pintype "passive"))
      (node (ref "U7") (pin "12") (pinfunction "12_12") (pintype "passive"))
    )
    (net (code "168") (name "Net-(J7-Pad3)") (class "Default")
      (node (ref "J7") (pin "3") (pinfunction "3_3") (pintype "passive"))
      (node (ref "U7") (pin "13") (pinfunction "13_13") (pintype "passive"))
    )
    (net (code "169") (name "Net-(J7-Pad4)") (class "Default")
      (node (ref "J7") (pin "4") (pinfunction "4_4") (pintype "passive"))
      (node (ref "U7") (pin "15") (pinfunction "15_15") (pintype "passive"))
    )
    (net (code "170") (name "Net-(J7-Pad5)") (class "Default")
      (node (ref "J7") (pin "5") (pinfunction "5_5") (pintype "passive"))
      (node (ref "U7") (pin "16") (pinfunction "16_16") (pintype "passive"))
    )
    (net (code "171") (name "Net-(J7-Pad6)") (class "Default")
      (node (ref "J7") (pin "6") (pinfunction "6_6") (pintype "passive"))
      (node (ref "U7") (pin "14") (pinfunction "14_14") (pintype "passive"))
    )
    (net (code "172") (name "Net-(J7-Pad7)") (class "Default")
      (node (ref "J7") (pin "7") (pinfunction "7_7") (pintype "passive"))
      (node (ref "U7") (pin "17") (pinfunction "17_17") (pintype "passive"))
    )
    (net (code "173") (name "Net-(J7-Pad8)") (class "Default")
      (node (ref "J7") (pin "8") (pinfunction "8_8") (pintype "passive"))
      (node (ref "U7") (pin "18") (pinfunction "18_18") (pintype "passive"))
    )
    (net (code "174") (name "Net-(R2-Pad2)") (class "Default")
      (node (ref "R2") (pin "2") (pinfunction "2_2") (pintype "passive"))
      (node (ref "U3") (pin "10") (pinfunction "10_10") (pintype "passive"))
      (node (ref "U4") (pin "10") (pinfunction "10_10") (pintype "passive"))
      (node (ref "U5") (pin "10") (pinfunction "10_10") (pintype "passive"))
      (node (ref "U6") (pin "10") (pinfunction "10_10") (pintype "passive"))
      (node (ref "U7") (pin "10") (pinfunction "10_10") (pintype "passive"))
    )
    (net (code "175") (name "unconnected-(J2-CC1-PadA5)") (class "Default")
      (node (ref "J2") (pin "A5") (pinfunction "CC1_A5") (pintype "passive"))
    )
    (net (code "176") (name "unconnected-(J2-CC2-PadB5)") (class "Default")
      (node (ref "J2") (pin "B5") (pinfunction "CC2_B5") (pintype "passive"))
    )
    (net (code "177") (name "unconnected-(P4-Pad36)") (class "Default")
      (node (ref "P4") (pin "36") (pinfunction "36_36") (pintype "passive"))
    )
    (net (code "178") (name "unconnected-(P5-Pad1)") (class "Default")
      (node (ref "P5") (pin "1") (pinfunction "1_1") (pintype "passive"))
    )
  )
)
